# schematic.net
KiCad netlist of a schematic drawn in EasyEDA
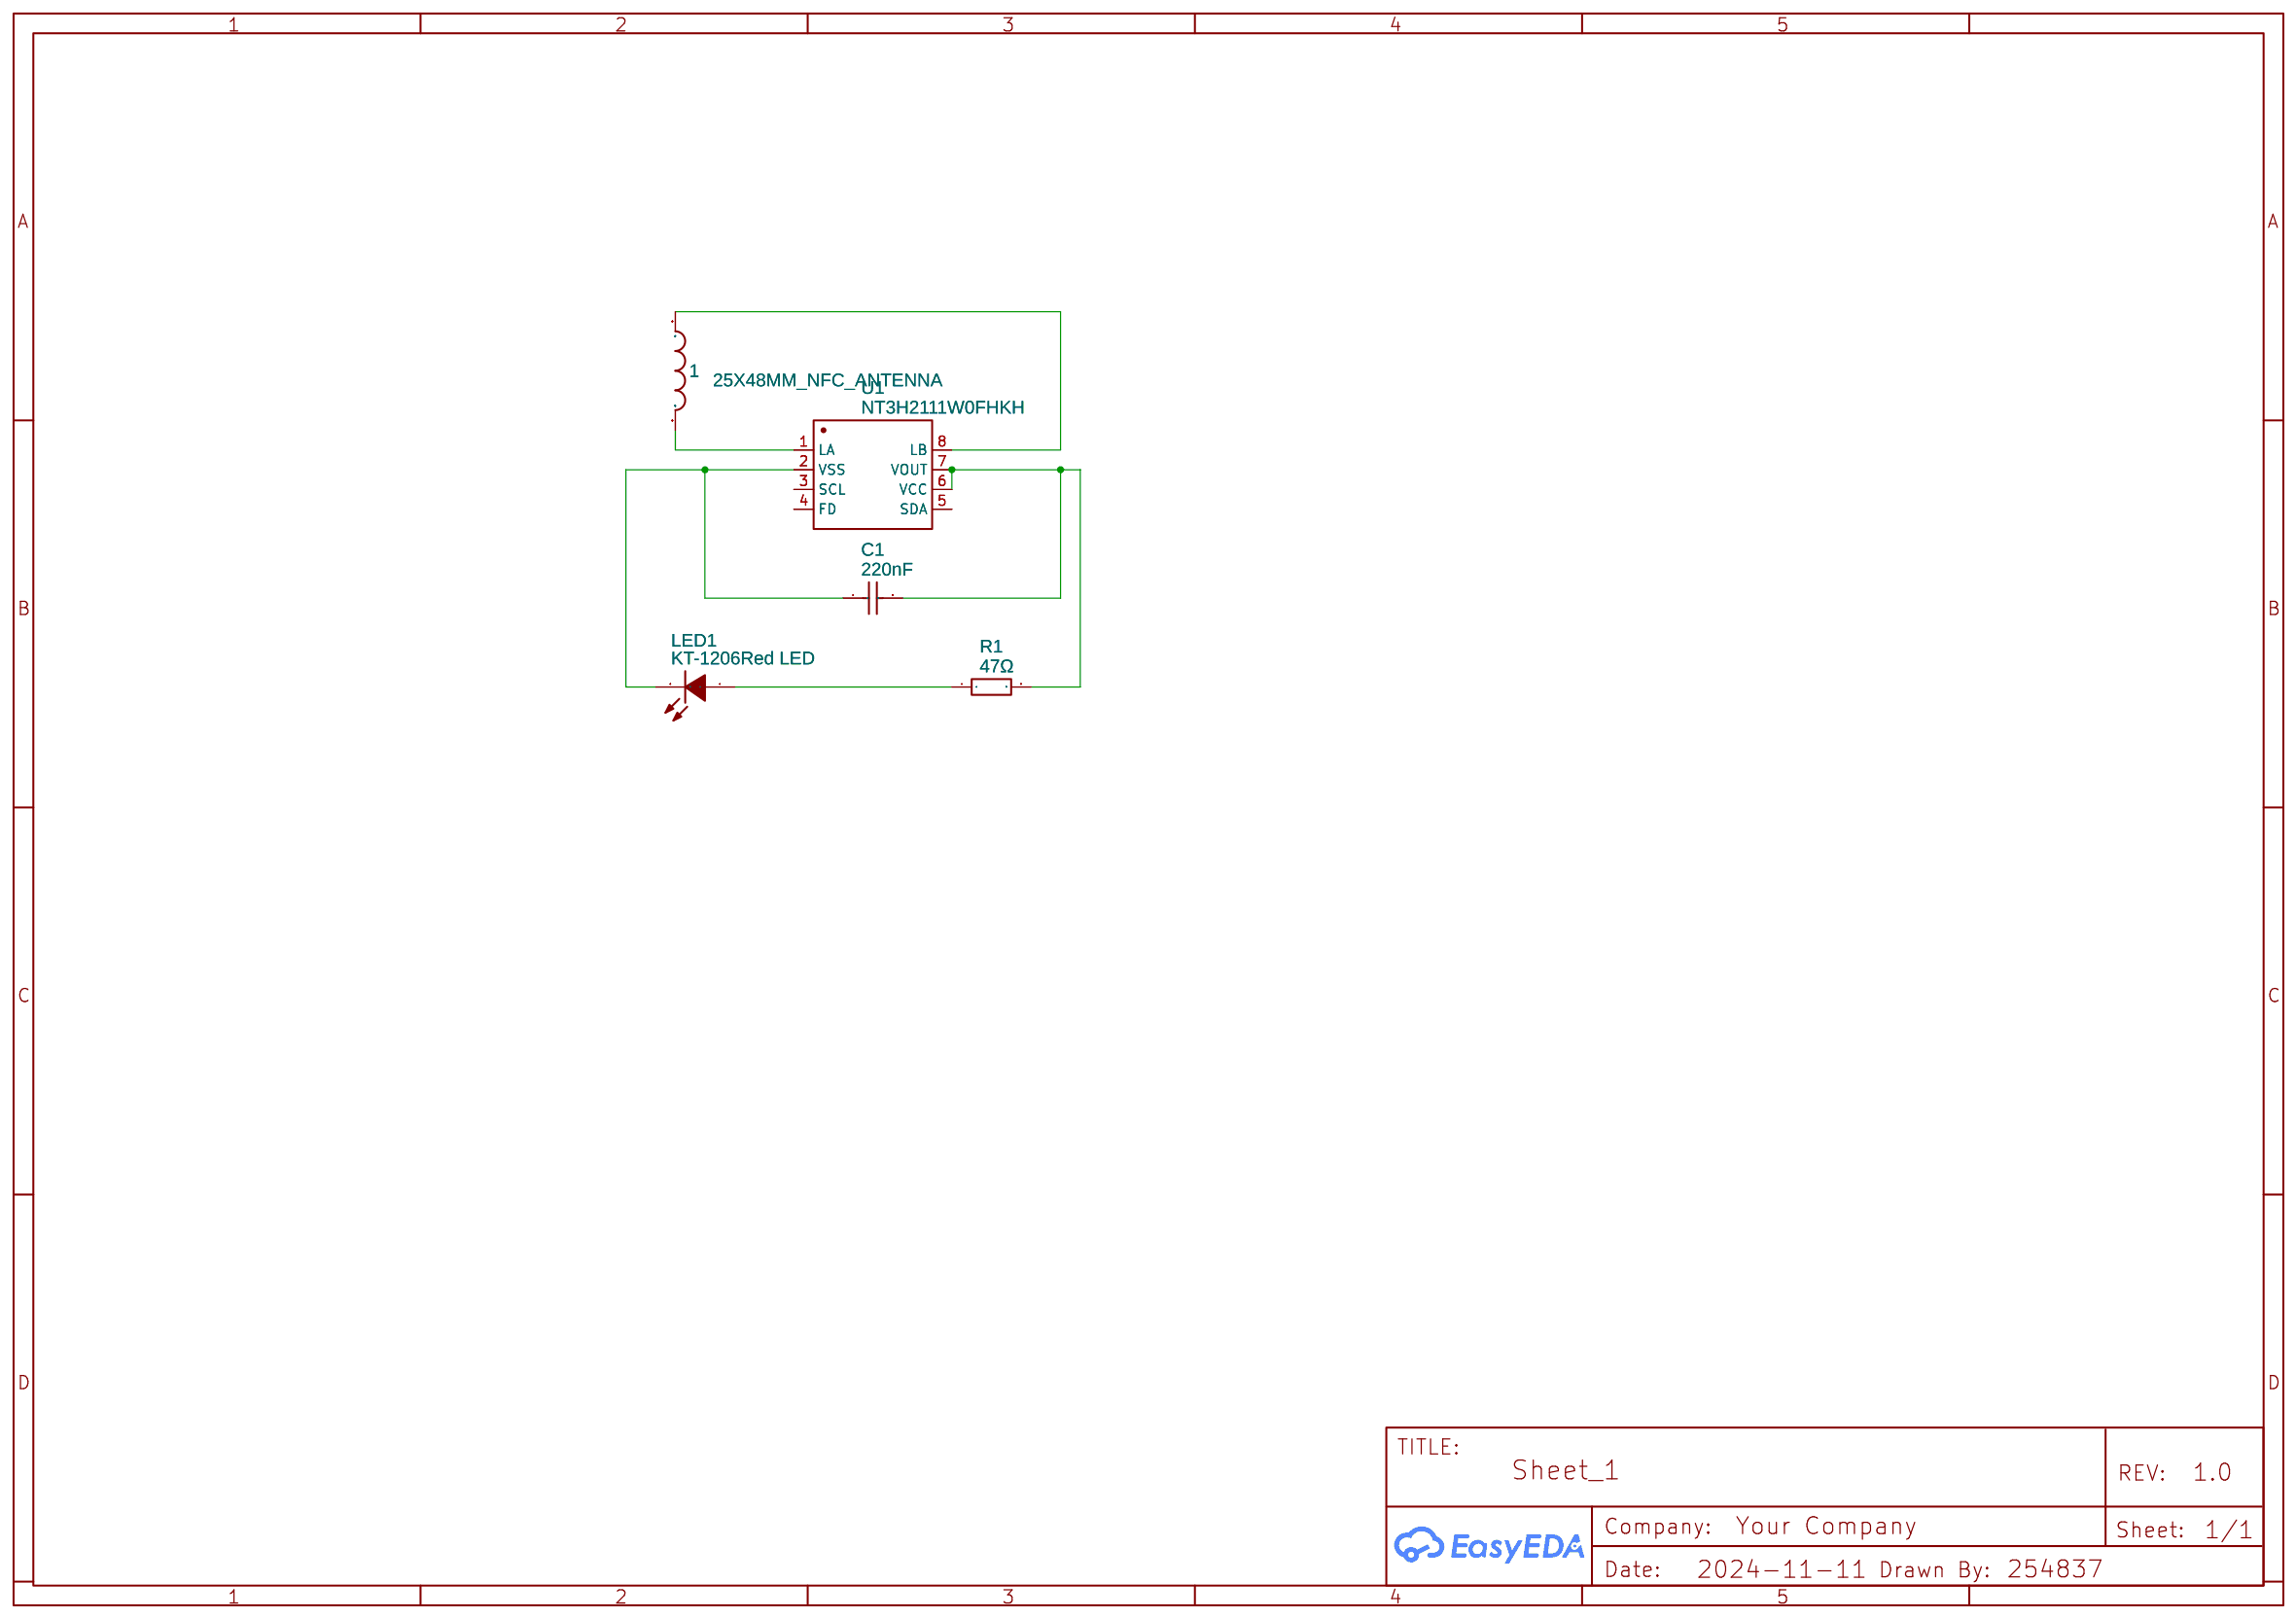
[diagram p0: schematic sheet]

(export (version "E")
  (design (tool "Eeschema 10.0.6"))
  (components
    (comp (ref "1") (value "25X48MM_NFC_ANTENNA") (libsource (lib "") (part "25X48MM_NFC_ANTENNA")))
    (comp (ref "C1")
      (value "220nF")
      (fields
        (field (name "Manufacturer Part") "CL10B224KA8NNNC")
        (field (name "Manufacturer") "SAMSUNG(三星)")
      )
      (libsource (lib "") (part "CL10B224KA8NNNC"))
    )
    (comp (ref "LED1")
      (value "KT-1206Red LED")
      (fields (field (name "Manufacturer Part") "KT-1206R") (field (name "Manufacturer") "KENTO"))
      (libsource (lib "") (part "KT-1206Red LED"))
    )
    (comp (ref "R1")
      (value "47Ω")
      (fields
        (field (name "Manufacturer Part") "0603WAF470JT5E")
        (field (name "Manufacturer") "UNI-ROYAL(厚声)")
      )
      (libsource (lib "") (part "0603WAF470JT5E"))
    )
    (comp (ref "U1")
      (value "NT3H2111W0FHKH")
      (fields (field (name "Manufacturer") "NXP(恩智浦)"))
      (libsource (lib "") (part "NT3H2111W0FHKH"))
    )
  )
  (nets
    (net (code "1") (name "Net-(LED1-A)") (class "Default")
      (node (ref "LED1") (pin "1") (pinfunction "A_1") (pintype "unspecified"))
      (node (ref "R1") (pin "1") (pinfunction "1_1") (pintype "input"))
    )
    (net (code "2") (name "Net-(LED1-K)") (class "Default")
      (node (ref "C1") (pin "1") (pinfunction "1_1") (pintype "input"))
      (node (ref "LED1") (pin "2") (pinfunction "K_2") (pintype "unspecified"))
      (node (ref "U1") (pin "2") (pinfunction "VSS_2") (pintype "unspecified"))
    )
    (net (code "3") (name "Net-(U1-LA)") (class "Default")
      (node (ref "1") (pin "P$2") (pinfunction "P$2_P$2") (pintype "bidirectional"))
      (node (ref "U1") (pin "1") (pinfunction "LA_1") (pintype "unspecified"))
    )
    (net (code "4") (name "Net-(U1-LB)") (class "Default")
      (node (ref "1") (pin "P$1") (pinfunction "P$1_P$1") (pintype "bidirectional"))
      (node (ref "U1") (pin "8") (pinfunction "LB_8") (pintype "unspecified"))
    )
    (net (code "5") (name "Net-(U1-VCC)") (class "Default")
      (node (ref "C1") (pin "2") (pinfunction "2_2") (pintype "input"))
      (node (ref "R1") (pin "2") (pinfunction "2_2") (pintype "input"))
      (node (ref "U1") (pin "6") (pinfunction "VCC_6") (pintype "unspecified"))
      (node (ref "U1") (pin "7") (pinfunction "VOUT_7") (pintype "unspecified"))
    )
    (net (code "6") (name "unconnected-(U1-FD-Pad4)") (class "Default")
      (node (ref "U1") (pin "4") (pinfunction "FD_4") (pintype "unspecified"))
    )
    (net (code "7") (name "unconnected-(U1-SCL-Pad3)") (class "Default")
      (node (ref "U1") (pin "3") (pinfunction "SCL_3") (pintype "unspecified"))
    )
    (net (code "8") (name "unconnected-(U1-SDA-Pad5)") (class "Default")
      (node (ref "U1") (pin "5") (pinfunction "SDA_5") (pintype "unspecified"))
    )
  )
)
